# SevenSegmentDriver.net
KiCad netlist of a schematic drawn in EAGLE
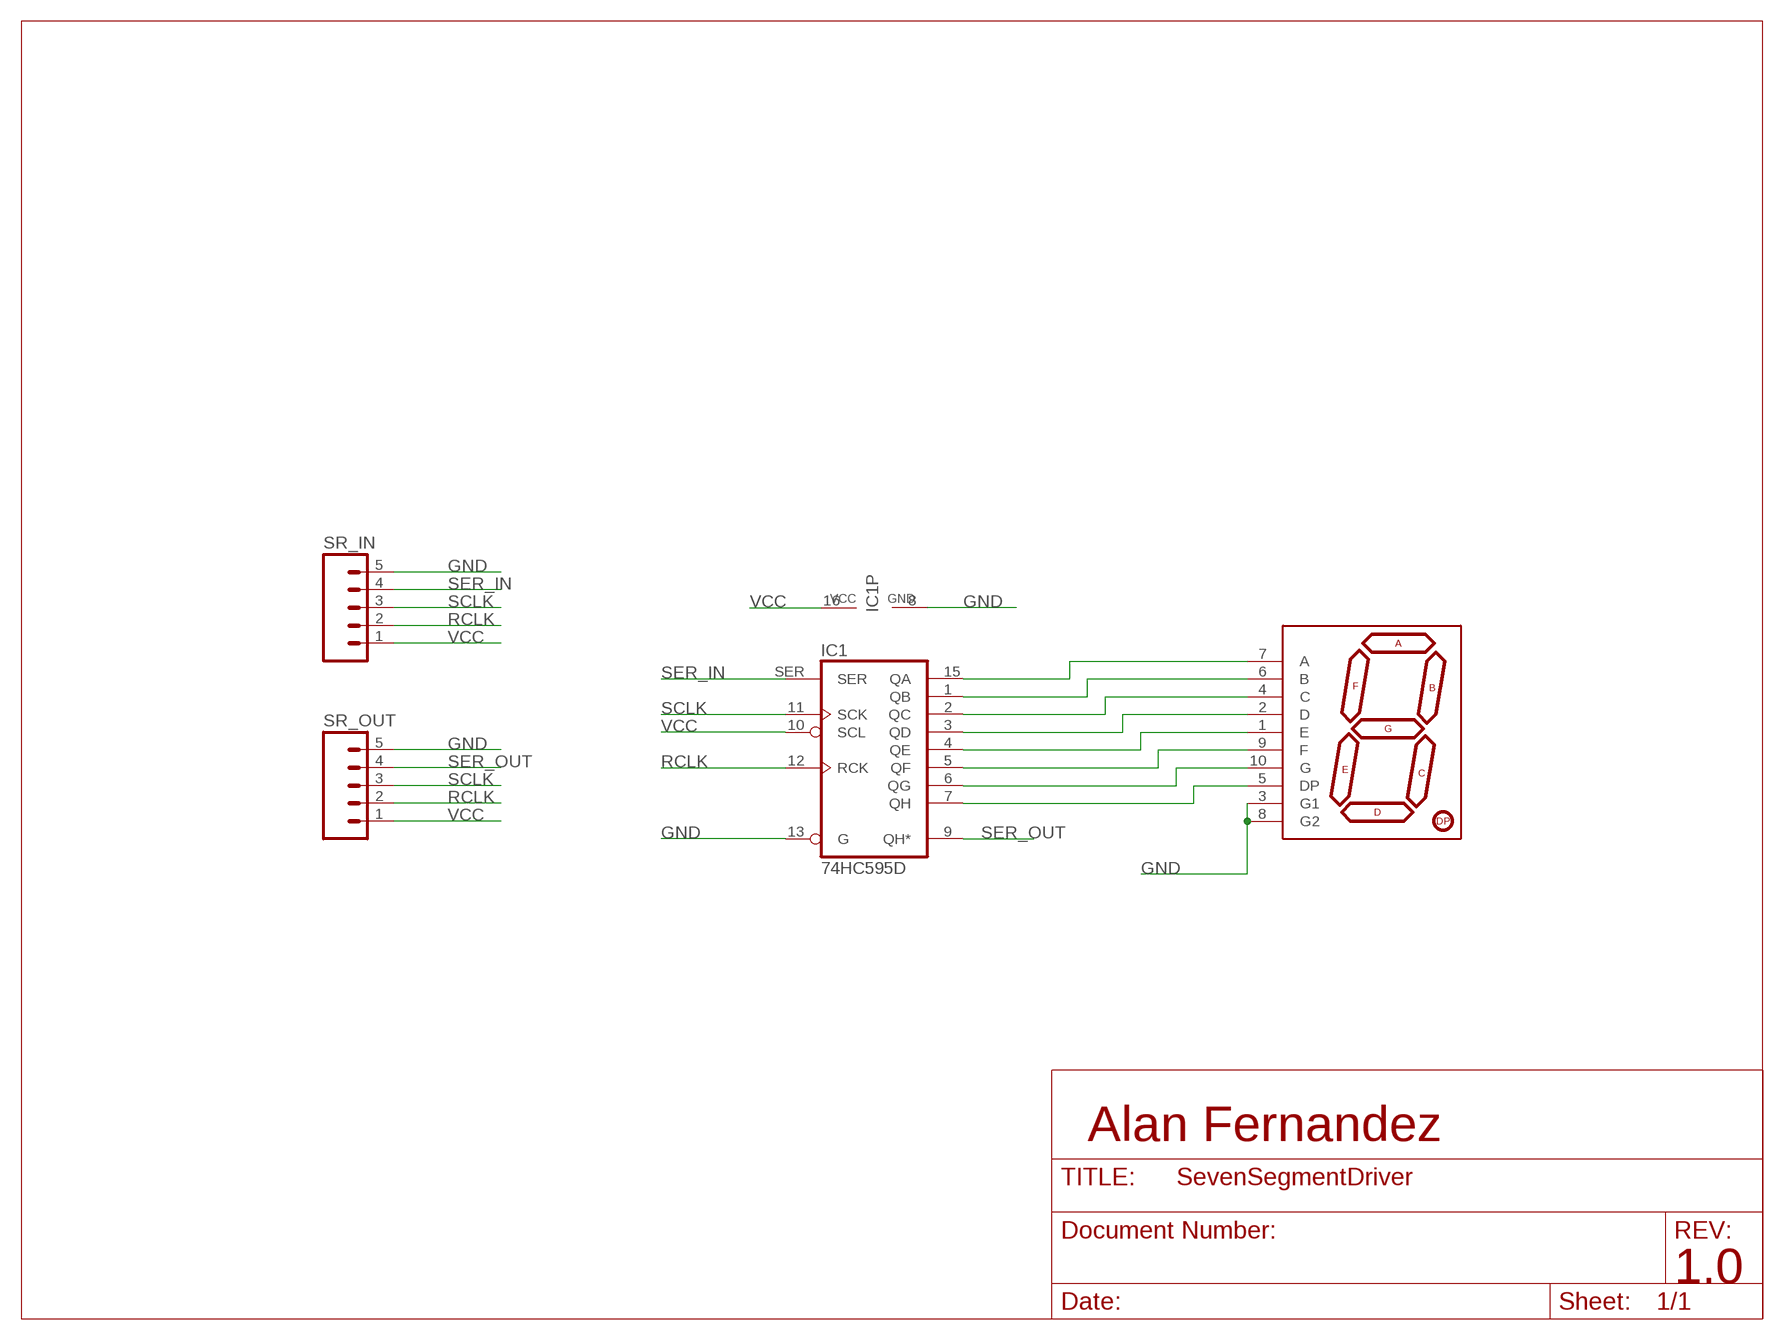
[diagram p0: schematic, sheet 1]

(export (version "E")
  (design (tool "Eeschema 10.0.6"))
  (components
    (comp (ref "IC1")
      (value "74HC595D")
      (footprint "eagle-import:SO16")
      (libsource (lib "eagle-import") (part "74595DHC"))
    )
    (comp (ref "SR_IN")
      (value "M05PTH")
      (footprint "eagle-import:1X05")
      (libsource (lib "eagle-import") (part "M05PTH"))
    )
    (comp (ref "SR_OUT")
      (value "M05PTH")
      (footprint "eagle-import:1X05")
      (libsource (lib "eagle-import") (part "M05PTH"))
    )
    (comp (ref "U$1")
      (value "7-SEGMENT-DISPLAY-1\"-REDEZ")
      (footprint "eagle-import:7-SEGMENT-1_PTH-EZ")
      (libsource (lib "eagle-import") (part "7-SEGMENT-DISPLAY-1{dblquote}-REDEZ"))
    )
  )
  (nets
    (net (code "1") (name "/GND") (class "Default")
      (node (ref "IC1") (pin "13") (pinfunction "G_13") (pintype "input"))
      (node (ref "IC1") (pin "8") (pinfunction "GND_8") (pintype "power_in"))
      (node (ref "SR_IN") (pin "5") (pinfunction "5_5") (pintype "passive"))
      (node (ref "SR_OUT") (pin "5") (pinfunction "5_5") (pintype "passive"))
      (node (ref "U$1") (pin "3") (pinfunction "G1_3") (pintype "bidirectional"))
      (node (ref "U$1") (pin "8") (pinfunction "G2_8") (pintype "bidirectional"))
    )
    (net (code "2") (name "/RCLK") (class "Default")
      (node (ref "IC1") (pin "12") (pinfunction "RCK_12") (pintype "input"))
      (node (ref "SR_IN") (pin "2") (pinfunction "2_2") (pintype "passive"))
      (node (ref "SR_OUT") (pin "2") (pinfunction "2_2") (pintype "passive"))
    )
    (net (code "3") (name "/SCLK") (class "Default")
      (node (ref "IC1") (pin "11") (pinfunction "SCK_11") (pintype "input"))
      (node (ref "SR_IN") (pin "3") (pinfunction "3_3") (pintype "passive"))
      (node (ref "SR_OUT") (pin "3") (pinfunction "3_3") (pintype "passive"))
    )
    (net (code "4") (name "/SER_IN") (class "Default")
      (node (ref "IC1") (pin "SER") (pinfunction "SER_SER") (pintype "input"))
      (node (ref "SR_IN") (pin "4") (pinfunction "4_4") (pintype "passive"))
    )
    (net (code "5") (name "/SER_OUT") (class "Default")
      (node (ref "IC1") (pin "9") (pinfunction "QH*_9") (pintype "tri_state"))
      (node (ref "SR_OUT") (pin "4") (pinfunction "4_4") (pintype "passive"))
    )
    (net (code "6") (name "/VCC") (class "Default")
      (node (ref "IC1") (pin "10") (pinfunction "SCL_10") (pintype "input"))
      (node (ref "IC1") (pin "16") (pinfunction "VCC_16") (pintype "power_in"))
      (node (ref "SR_IN") (pin "1") (pinfunction "1_1") (pintype "passive"))
      (node (ref "SR_OUT") (pin "1") (pinfunction "1_1") (pintype "passive"))
    )
    (net (code "7") (name "Net-(IC1A-QA)") (class "Default")
      (node (ref "IC1") (pin "15") (pinfunction "QA_15") (pintype "tri_state"))
      (node (ref "U$1") (pin "7") (pinfunction "A_7") (pintype "bidirectional"))
    )
    (net (code "8") (name "Net-(IC1A-QB)") (class "Default")
      (node (ref "IC1") (pin "1") (pinfunction "QB_1") (pintype "tri_state"))
      (node (ref "U$1") (pin "6") (pinfunction "B_6") (pintype "bidirectional"))
    )
    (net (code "9") (name "Net-(IC1A-QC)") (class "Default")
      (node (ref "IC1") (pin "2") (pinfunction "QC_2") (pintype "tri_state"))
      (node (ref "U$1") (pin "4") (pinfunction "C_4") (pintype "bidirectional"))
    )
    (net (code "10") (name "Net-(IC1A-QD)") (class "Default")
      (node (ref "IC1") (pin "3") (pinfunction "QD_3") (pintype "tri_state"))
      (node (ref "U$1") (pin "2") (pinfunction "D_2") (pintype "bidirectional"))
    )
    (net (code "11") (name "Net-(IC1A-QE)") (class "Default")
      (node (ref "IC1") (pin "4") (pinfunction "QE_4") (pintype "tri_state"))
      (node (ref "U$1") (pin "1") (pinfunction "E_1") (pintype "bidirectional"))
    )
    (net (code "12") (name "Net-(IC1A-QF)") (class "Default")
      (node (ref "IC1") (pin "5") (pinfunction "QF_5") (pintype "tri_state"))
      (node (ref "U$1") (pin "9") (pinfunction "F_9") (pintype "bidirectional"))
    )
    (net (code "13") (name "Net-(IC1A-QG)") (class "Default")
      (node (ref "IC1") (pin "6") (pinfunction "QG_6") (pintype "tri_state"))
      (node (ref "U$1") (pin "10") (pinfunction "G_10") (pintype "bidirectional"))
    )
    (net (code "14") (name "Net-(IC1A-QH)") (class "Default")
      (node (ref "IC1") (pin "7") (pinfunction "QH_7") (pintype "tri_state"))
      (node (ref "U$1") (pin "5") (pinfunction "DP_5") (pintype "bidirectional"))
    )
  )
)
